# mpcie-breakout.net
KiCad netlist of a schematic drawn in EAGLE
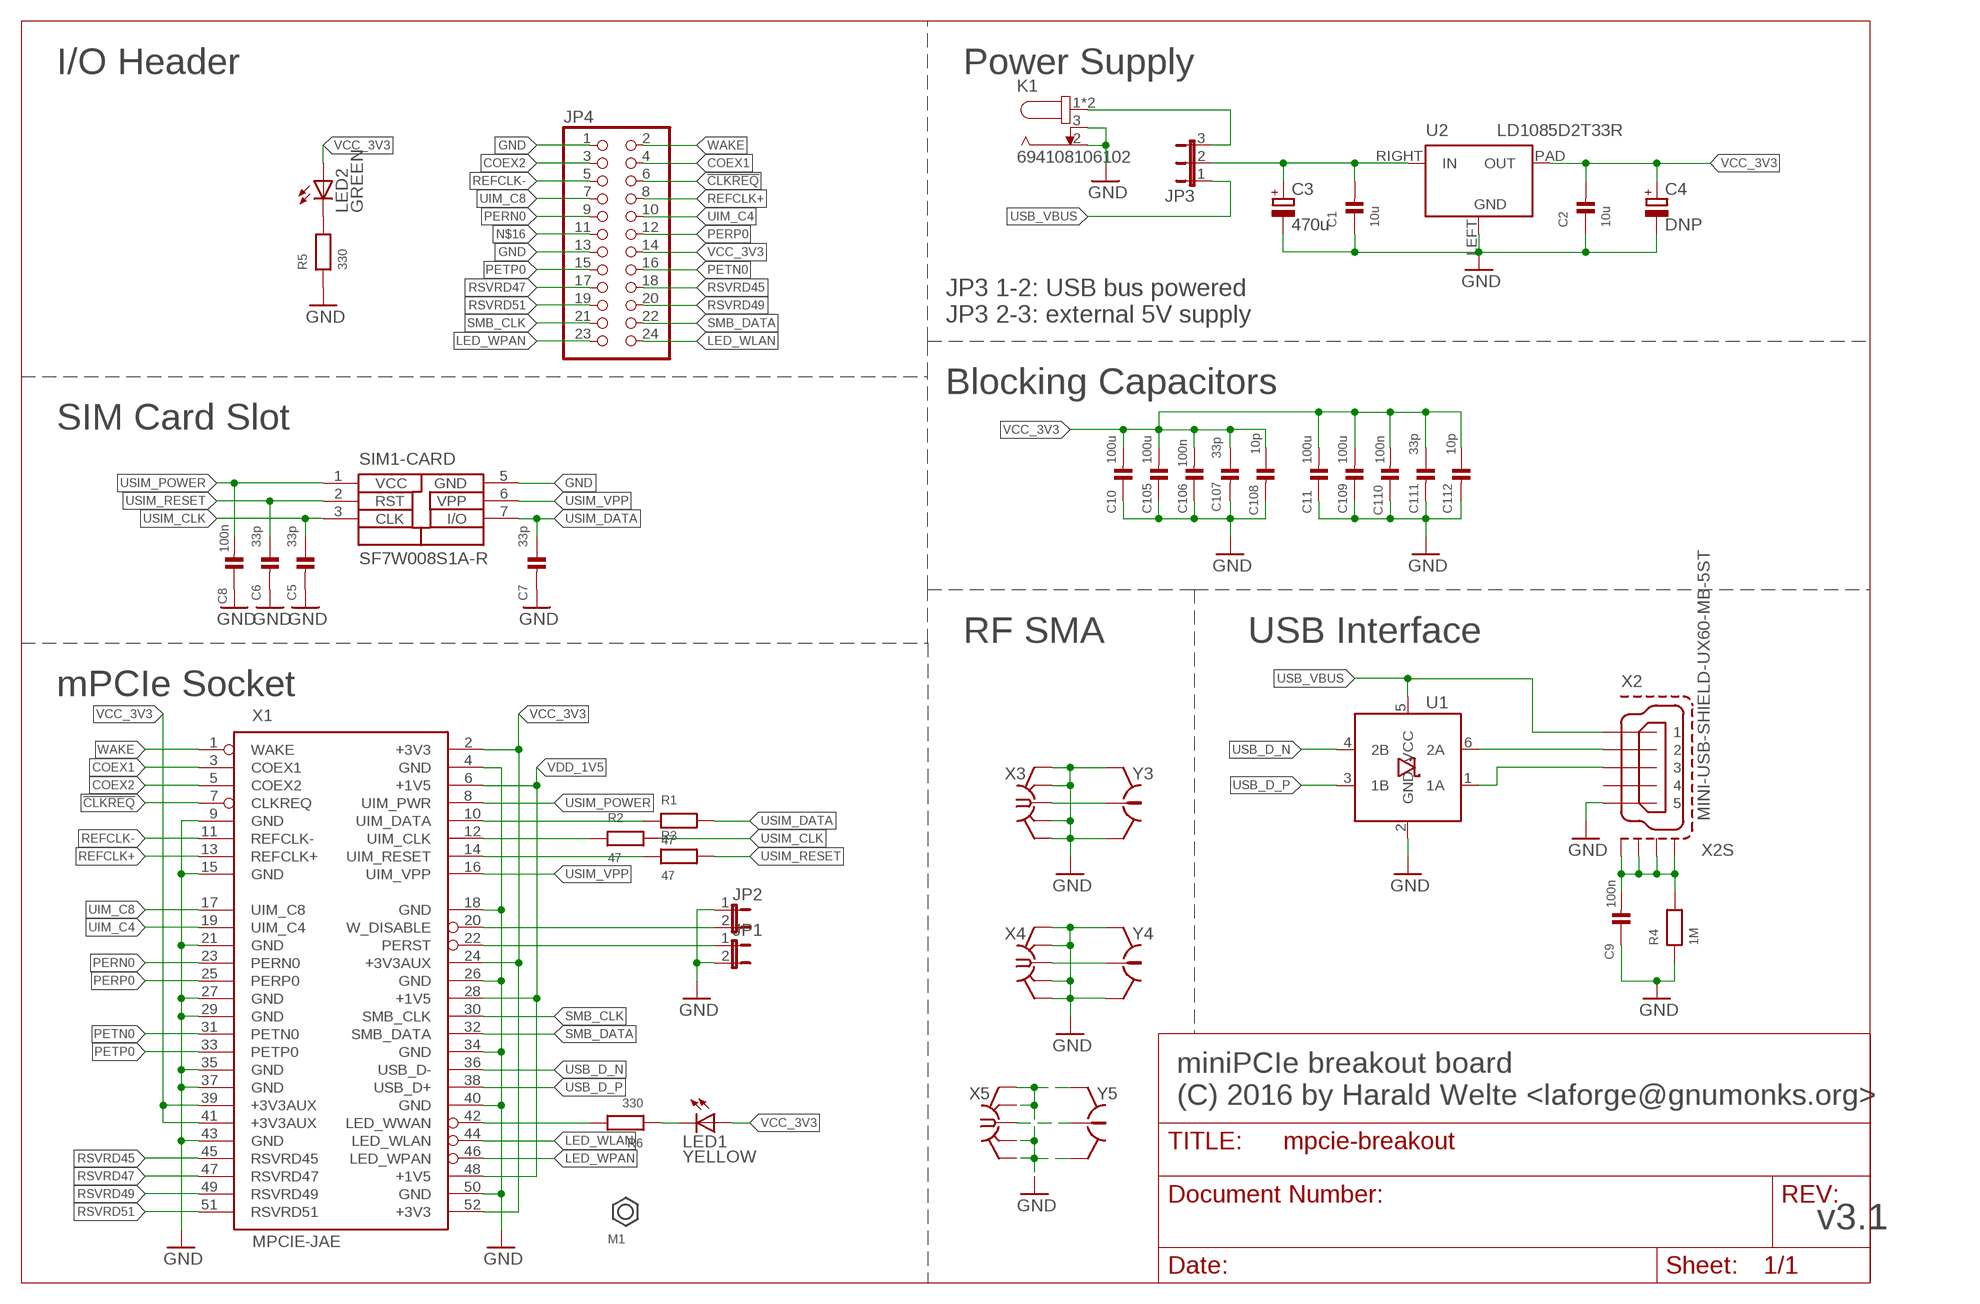
[diagram p0: schematic, sheet 1]

(export (version "E")
  (design (tool "Eeschema 10.0.6"))
  (components
    (comp (ref "C1")
      (value "10u")
      (footprint "eagle-import:_0805")
      (description "10µF 16V Ceramic Capacitor X5R 0805 (2012 Metric) 0.079\" L x 0.049\" W (2.00mm x 1.25mm)")
      (fields
        (field (name "MANUFACTURER") "Samsung Electro-Mechanics America, Inc.")
        (field (name "MANUFACTURERPARTNUMBER") "CL21A106KOQNNNG")
      )
      (libsource (lib "eagle-import") (part "CAP_CERAMIC_0805"))
    )
    (comp (ref "C2")
      (value "10u")
      (footprint "eagle-import:_0805")
      (description "10µF 16V Ceramic Capacitor X5R 0805 (2012 Metric) 0.079\" L x 0.049\" W (2.00mm x 1.25mm)")
      (fields
        (field (name "MANUFACTURER") "Samsung Electro-Mechanics America, Inc.")
        (field (name "MANUFACTURERPARTNUMBER") "CL21A106KOQNNNG")
      )
      (libsource (lib "eagle-import") (part "CAP_CERAMIC_0805"))
    )
    (comp (ref "C3")
      (value "470u")
      (footprint "eagle-import:UD-8X10_NICHICON")
      (description "470µF 6.3V Aluminum Capacitors Radial, Can - SMD  2000 Hrs @ 85°C")
      (fields
        (field (name "MANUFACTURER") "Nichicon")
        (field (name "MANUFACTURERPARTNUMBER") "UUR0J471MNL1GS")
      )
      (libsource (lib "eagle-import") (part "CPOL-EUUD-8X10"))
    )
    (comp (ref "C4")
      (value "DNP")
      (footprint "eagle-import:SMC_E")
      (description "NO DESCRIPTION")
      (fields
        (field (name "MANUFACTURER") "UNKNOWN MANUFACTURER")
        (field (name "MANUFACTURERPARTNUMBER") "UNKNOWN MANUFACTURER PART NUMBER")
      )
      (libsource (lib "eagle-import") (part "CPOL-EUSMCE"))
    )
    (comp (ref "C5")
      (value "33p")
      (footprint "eagle-import:_0402")
      (description "CAP CER 33PF 50V NP0 0402")
      (fields
        (field (name "MANUFACTURER") "Samsung Electro-Mechanics America, Inc.")
        (field (name "MANUFACTURERPARTNUMBER") "CL05C330JB5NNNC")
      )
      (libsource (lib "eagle-import") (part "CAP_CERAMIC_0402"))
    )
    (comp (ref "C6")
      (value "33p")
      (footprint "eagle-import:_0402")
      (description "CAP CER 33PF 50V NP0 0402")
      (fields
        (field (name "MANUFACTURER") "Samsung Electro-Mechanics America, Inc.")
        (field (name "MANUFACTURERPARTNUMBER") "CL05C330JB5NNNC")
      )
      (libsource (lib "eagle-import") (part "CAP_CERAMIC_0402"))
    )
    (comp (ref "C7")
      (value "33p")
      (footprint "eagle-import:_0402")
      (description "CAP CER 33PF 50V NP0 0402")
      (fields
        (field (name "MANUFACTURER") "Samsung Electro-Mechanics America, Inc.")
        (field (name "MANUFACTURERPARTNUMBER") "CL05C330JB5NNNC")
      )
      (libsource (lib "eagle-import") (part "CAP_CERAMIC_0402"))
    )
    (comp (ref "C8")
      (value "100n")
      (footprint "eagle-import:_0603")
      (description "CAP CER 0.1UF 16V 10% X7R 0603")
      (fields
        (field (name "MANUFACTURER") "Samsung Electro-Mechanics America, Inc")
        (field (name "MANUFACTURERPARTNUMBER") "CL10B104KO8NNNC")
      )
      (libsource (lib "eagle-import") (part "CAP_CERAMIC_0603"))
    )
    (comp (ref "C9")
      (value "100n")
      (footprint "eagle-import:_0603")
      (description "CAP CER 0.1UF 16V 10% X7R 0603")
      (fields
        (field (name "MANUFACTURER") "Samsung Electro-Mechanics America, Inc")
        (field (name "MANUFACTURERPARTNUMBER") "CL10B104KO8NNNC")
      )
      (libsource (lib "eagle-import") (part "CAP_CERAMIC_0603"))
    )
    (comp (ref "C10")
      (value "100u")
      (footprint "eagle-import:1206")
      (description "100µF 6.3V Ceramic Capacitor X5R 1206 (3216 Metric) 0.126\" L x 0.063\" W (3.20mm x 1.60mm)")
      (fields
        (field (name "MANUFACTURER") "Murata Electronics North America")
        (field (name "MANUFACTURERPARTNUMBER") "GRM31CR60J107ME39K")
      )
      (libsource (lib "eagle-import") (part "CAP_CERAMIC1206"))
    )
    (comp (ref "C11")
      (value "100u")
      (footprint "eagle-import:1206")
      (description "100µF 6.3V Ceramic Capacitor X5R 1206 (3216 Metric) 0.126\" L x 0.063\" W (3.20mm x 1.60mm)")
      (fields
        (field (name "MANUFACTURER") "Murata Electronics North America")
        (field (name "MANUFACTURERPARTNUMBER") "GRM31CR60J107ME39K")
      )
      (libsource (lib "eagle-import") (part "CAP_CERAMIC1206"))
    )
    (comp (ref "C105")
      (value "100u")
      (footprint "eagle-import:1206")
      (description "100µF 6.3V Ceramic Capacitor X5R 1206 (3216 Metric) 0.126\" L x 0.063\" W (3.20mm x 1.60mm)")
      (fields
        (field (name "MANUFACTURER") "Murata Electronics North America")
        (field (name "MANUFACTURERPARTNUMBER") "GRM31CR60J107ME39K")
      )
      (libsource (lib "eagle-import") (part "CAP_CERAMIC1206"))
    )
    (comp (ref "C106")
      (value "100n")
      (footprint "eagle-import:_0603")
      (description "CAP CER 0.1UF 16V 10% X7R 0603")
      (fields
        (field (name "MANUFACTURER") "Samsung Electro-Mechanics America, Inc")
        (field (name "MANUFACTURERPARTNUMBER") "CL10B104KO8NNNC")
      )
      (libsource (lib "eagle-import") (part "CAP_CERAMIC_0603"))
    )
    (comp (ref "C107")
      (value "33p")
      (footprint "eagle-import:_0402")
      (description "CAP CER 33PF 50V NP0 0402")
      (fields
        (field (name "MANUFACTURER") "Samsung Electro-Mechanics America, Inc.")
        (field (name "MANUFACTURERPARTNUMBER") "CL05C330JB5NNNC")
      )
      (libsource (lib "eagle-import") (part "CAP_CERAMIC_0402"))
    )
    (comp (ref "C108")
      (value "10p")
      (footprint "eagle-import:_0603")
      (description "CAP CER 10PF 50V NP0 0603")
      (fields
        (field (name "MANUFACTURER") "Kemet")
        (field (name "MANUFACTURERPARTNUMBER") "C0603C100J5GACTU")
      )
      (libsource (lib "eagle-import") (part "CAP_CERAMIC_0603"))
    )
    (comp (ref "C109")
      (value "100u")
      (footprint "eagle-import:1206")
      (description "100µF 6.3V Ceramic Capacitor X5R 1206 (3216 Metric) 0.126\" L x 0.063\" W (3.20mm x 1.60mm)")
      (fields
        (field (name "MANUFACTURER") "Murata Electronics North America")
        (field (name "MANUFACTURERPARTNUMBER") "GRM31CR60J107ME39K")
      )
      (libsource (lib "eagle-import") (part "CAP_CERAMIC1206"))
    )
    (comp (ref "C110")
      (value "100n")
      (footprint "eagle-import:_0603")
      (description "CAP CER 0.1UF 16V 10% X7R 0603")
      (fields
        (field (name "MANUFACTURER") "Samsung Electro-Mechanics America, Inc")
        (field (name "MANUFACTURERPARTNUMBER") "CL10B104KO8NNNC")
      )
      (libsource (lib "eagle-import") (part "CAP_CERAMIC_0603"))
    )
    (comp (ref "C111")
      (value "33p")
      (footprint "eagle-import:_0402")
      (description "CAP CER 33PF 50V NP0 0402")
      (fields
        (field (name "MANUFACTURER") "Samsung Electro-Mechanics America, Inc.")
        (field (name "MANUFACTURERPARTNUMBER") "CL05C330JB5NNNC")
      )
      (libsource (lib "eagle-import") (part "CAP_CERAMIC_0402"))
    )
    (comp (ref "C112")
      (value "10p")
      (footprint "eagle-import:_0603")
      (description "CAP CER 10PF 50V NP0 0603")
      (fields
        (field (name "MANUFACTURER") "Kemet")
        (field (name "MANUFACTURERPARTNUMBER") "C0603C100J5GACTU")
      )
      (libsource (lib "eagle-import") (part "CAP_CERAMIC_0603"))
    )
    (comp (ref "JP1")
      (value "JP1E")
      (footprint "eagle-import:JP1")
      (description "NO DESCRIPTION")
      (fields
        (field (name "MANUFACTURER") "UNKNOWN MANUFACTURER")
        (field (name "MANUFACTURERPARTNUMBER") "UNKNOWN MANUFACTURER PART NUMBER")
      )
      (libsource (lib "eagle-import") (part "JP1E"))
    )
    (comp (ref "JP2")
      (value "JP1E")
      (footprint "eagle-import:JP1")
      (description "NO DESCRIPTION")
      (fields
        (field (name "MANUFACTURER") "UNKNOWN MANUFACTURER")
        (field (name "MANUFACTURERPARTNUMBER") "UNKNOWN MANUFACTURER PART NUMBER")
      )
      (libsource (lib "eagle-import") (part "JP1E"))
    )
    (comp (ref "JP3")
      (value "JP2E")
      (footprint "eagle-import:JP2")
      (description "NO DESCRIPTION")
      (fields
        (field (name "MANUFACTURER") "UNKNOWN MANUFACTURER")
        (field (name "MANUFACTURERPARTNUMBER") "UNKNOWN MANUFACTURER PART NUMBER")
      )
      (libsource (lib "eagle-import") (part "JP2E"))
    )
    (comp (ref "JP4")
      (value "PINHD-2X12")
      (footprint "eagle-import:2X12")
      (description "24 Positions Header, Unshrouded Connector 0.100\" (2.54mm) Through Hole Gold")
      (fields (field (name "MANUFACTURER") "3M") (field (name "MANUFACTURERPARTNUMBER") "961224-6404-AR"))
      (libsource (lib "eagle-import") (part "PINHD-2X12"))
    )
    (comp (ref "K1")
      (value "694108106102")
      (footprint "eagle-import:694108106102")
      (description "Power Barrel Connector Jack 2.50mm ID (0.098\"), 5.50mm OD (0.217\") Surface Mount, Right Angle")
      (fields (field (name "MANUFACTURER") "Wurth Electronics Inc"))
      (libsource (lib "eagle-import") (part "694108106102"))
    )
    (comp (ref "LED1")
      (value "YELLOW")
      (footprint "eagle-import:CHIP-LED0603")
      (description "NO DESCRIPTION")
      (fields
        (field (name "MANUFACTURER") "UNKNOWN MANUFACTURER")
        (field (name "MANUFACTURERPARTNUMBER") "UNKNOWN MANUFACTURER PART NUMBER")
      )
      (libsource (lib "eagle-import") (part "LEDCHIP-LED0603"))
    )
    (comp (ref "LED2")
      (value "GREEN")
      (footprint "eagle-import:CHIP-LED0603")
      (description "NO DESCRIPTION")
      (fields
        (field (name "MANUFACTURER") "UNKNOWN MANUFACTURER")
        (field (name "MANUFACTURERPARTNUMBER") "UNKNOWN MANUFACTURER PART NUMBER")
      )
      (libsource (lib "eagle-import") (part "LEDCHIP-LED0603"))
    )
    (comp (ref "R1")
      (value "47")
      (footprint "eagle-import:_0603")
      (description "RES SMD 47 OHM 5% 1/10W 0603")
      (fields (field (name "MANUFACTURER") "Yageo") (field (name "MANUFACTURERPARTNUMBER") "RC0603JR-0747RL"))
      (libsource (lib "eagle-import") (part "RESISTOR_0603"))
    )
    (comp (ref "R2")
      (value "47")
      (footprint "eagle-import:_0603")
      (description "RES SMD 47 OHM 5% 1/10W 0603")
      (fields (field (name "MANUFACTURER") "Yageo") (field (name "MANUFACTURERPARTNUMBER") "RC0603JR-0747RL"))
      (libsource (lib "eagle-import") (part "RESISTOR_0603"))
    )
    (comp (ref "R3")
      (value "47")
      (footprint "eagle-import:_0603")
      (description "RES SMD 47 OHM 5% 1/10W 0603")
      (fields (field (name "MANUFACTURER") "Yageo") (field (name "MANUFACTURERPARTNUMBER") "RC0603JR-0747RL"))
      (libsource (lib "eagle-import") (part "RESISTOR_0603"))
    )
    (comp (ref "R4")
      (value "1M")
      (footprint "eagle-import:_0603")
      (description "RES SMD 1M OHM 5% 1/10W 0603")
      (fields (field (name "MANUFACTURER") "Yageo") (field (name "MANUFACTURERPARTNUMBER") "RC0603JR-071ML"))
      (libsource (lib "eagle-import") (part "RESISTOR_0603"))
    )
    (comp (ref "R5")
      (value "330")
      (footprint "eagle-import:_0603")
      (description "RES SMD 330 OHM 5% 1/10W 0603")
      (fields
        (field (name "MANUFACTURER") "Yageo")
        (field (name "MANUFACTURERPARTNUMBER") "RC0603JR-07330RL")
      )
      (libsource (lib "eagle-import") (part "RESISTOR_0603"))
    )
    (comp (ref "R6")
      (value "330")
      (footprint "eagle-import:_0603")
      (description "RES SMD 330 OHM 5% 1/10W 0603")
      (fields
        (field (name "MANUFACTURER") "Yageo")
        (field (name "MANUFACTURERPARTNUMBER") "RC0603JR-07330RL")
      )
      (libsource (lib "eagle-import") (part "RESISTOR_0603"))
    )
    (comp (ref "SIM1")
      (value "SF7W008S1A-R")
      (footprint "eagle-import:SF7W008S1A-RESTR")
      (description "8 (6 + 2) Position Card Connector SIM Card Surface Mount, Right Angle Gold")
      (fields
        (field (name "MANUFACTURER") "JAE Electronics")
        (field (name "MANUFACTURERPARTNUMBER") "SF7W008S1AE900")
      )
      (libsource (lib "eagle-import") (part "SF7W008S1A-R"))
    )
    (comp (ref "U1")
      (value "IP4234CZ6")
      (footprint "eagle-import:TSOP-6")
      (description "TVS DIODE 5.5VWM 6TSOP")
      (fields
        (field (name "MANUFACTURER") "NXP Semiconductors")
        (field (name "MANUFACTURERPARTNUMBER") "IP4234CZ6,125")
      )
      (libsource (lib "eagle-import") (part "IP4234CZ6"))
    )
    (comp (ref "U2")
      (value "LD1085D2T33R")
      (footprint "eagle-import:ST_D2PAK")
      (description "Linear Voltage Regulator IC Positive Fixed 1 Output 3.3V 3A D2PAK")
      (fields (field (name "MANUFACTURER") "STMicroelectronics"))
      (libsource (lib "eagle-import") (part "LDO-LD1085D2"))
    )
    (comp (ref "X1")
      (value "MPCIE-JAE")
      (footprint "eagle-import:MM60-52")
      (description "CONN MINI EXPRESS CARD 52POS SMD")
      (fields
        (field (name "MANUFACTURER") "JAE Electronics")
        (field (name "MANUFACTURERPARTNUMBER") "MM60-52B1-E1-R650")
      )
      (libsource (lib "eagle-import") (part "MPCIE-JAE"))
    )
    (comp (ref "X2")
      (value "MINI-USB-SHIELD-UX60-MB-5ST")
      (footprint "eagle-import:UX60-MB-5ST")
      (description "USB - mini B USB 2.0 Receptacle Connector 5 Position Surface Mount, Right Angle, Horizontal")
      (fields
        (field (name "CLASS") "CONNECTOR")
        (field (name "LINK") "http://www.digikey.com/product-detail/en/hirose-electric-co-ltd/UX60-MB-5ST/H2959CT-ND/597538")
        (field (name "MANUFACTURER") "Hirose Electric Co Ltd")
        (field (name "MANUFACTURERPARTNUMBER") "UX60-MB-5ST")
        (field (name "POPULATED") "TRUE")
        (field (name "ROHSCERTIFICATE") "UNKNOWN ROHS CERTIFICATE")
        (field (name "SOURCE") "DIGIKEY")
        (field (name "SOURCEPARTNUMBER") "H2959CT-ND")
      )
      (libsource (lib "eagle-import") (part "MINI-USB-SHIELD-UX60-MB-5ST"))
    )
    (comp (ref "X3")
      (value "SMA-F-S-TH")
      (footprint "eagle-import:SMA-F-S-TH")
      (description "CONN SMA JACK STR 50 OHM PCB")
      (fields
        (field (name "MANUFACTURER") "TE Connectivity AMP Connectors")
        (field (name "MANUFACTURERPARTNUMBER") "5-1814832-1")
      )
      (libsource (lib "eagle-import") (part "SMA-F-S-TH"))
    )
    (comp (ref "X4")
      (value "SMA-F-S-TH")
      (footprint "eagle-import:SMA-F-S-TH")
      (description "CONN SMA JACK STR 50 OHM PCB")
      (fields
        (field (name "MANUFACTURER") "TE Connectivity AMP Connectors")
        (field (name "MANUFACTURERPARTNUMBER") "5-1814832-1")
      )
      (libsource (lib "eagle-import") (part "SMA-F-S-TH"))
    )
    (comp (ref "X5")
      (value "SMA-F-S-TH")
      (footprint "eagle-import:SMA-F-S-TH")
      (description "CONN SMA JACK STR 50 OHM PCB")
      (fields
        (field (name "MANUFACTURER") "TE Connectivity AMP Connectors")
        (field (name "MANUFACTURERPARTNUMBER") "5-1814832-1")
      )
      (libsource (lib "eagle-import") (part "SMA-F-S-TH"))
    )
    (comp (ref "Y3")
      (value "HRS_UFL")
      (footprint "eagle-import:HRS_UFL")
      (description "CONN UMC RCPT STR 50 OHM SMD")
      (fields
        (field (name "MANUFACTURER") "Hirose Electric Co Ltd")
        (field (name "MANUFACTURERPARTNUMBER") "U.FL-R-SMT(01)")
      )
      (libsource (lib "eagle-import") (part "HRS_UFL"))
    )
    (comp (ref "Y4")
      (value "HRS_UFL")
      (footprint "eagle-import:HRS_UFL")
      (description "CONN UMC RCPT STR 50 OHM SMD")
      (fields
        (field (name "MANUFACTURER") "Hirose Electric Co Ltd")
        (field (name "MANUFACTURERPARTNUMBER") "U.FL-R-SMT(01)")
      )
      (libsource (lib "eagle-import") (part "HRS_UFL"))
    )
    (comp (ref "Y5")
      (value "HRS_UFL")
      (footprint "eagle-import:HRS_UFL")
      (description "CONN UMC RCPT STR 50 OHM SMD")
      (fields
        (field (name "MANUFACTURER") "Hirose Electric Co Ltd")
        (field (name "MANUFACTURERPARTNUMBER") "U.FL-R-SMT(01)")
      )
      (libsource (lib "eagle-import") (part "HRS_UFL"))
    )
  )
  (nets
    (net (code "1") (name "/~{CLKREQ}") (class "Default")
      (node (ref "JP4") (pin "6") (pinfunction "6_6") (pintype "passive"))
      (node (ref "X1") (pin "7") (pinfunction "CLKREQ_7") (pintype "output"))
    )
    (net (code "2") (name "COEX1") (class "Default")
      (node (ref "JP4") (pin "4") (pinfunction "4_4") (pintype "passive"))
      (node (ref "X1") (pin "3") (pinfunction "COEX1_3") (pintype "bidirectional"))
    )
    (net (code "3") (name "COEX2") (class "Default")
      (node (ref "JP4") (pin "3") (pinfunction "3_3") (pintype "passive"))
      (node (ref "X1") (pin "5") (pinfunction "COEX2_5") (pintype "bidirectional"))
    )
    (net (code "4") (name "GND") (class "Default")
      (node (ref "C1") (pin "1") (pinfunction "1_1") (pintype "passive"))
      (node (ref "C10") (pin "1") (pinfunction "1_1") (pintype "passive"))
      (node (ref "C105") (pin "1") (pinfunction "1_1") (pintype "passive"))
      (node (ref "C106") (pin "1") (pinfunction "1_1") (pintype "passive"))
      (node (ref "C107") (pin "2") (pinfunction "2_2") (pintype "passive"))
      (node (ref "C108") (pin "2") (pinfunction "2_2") (pintype "passive"))
      (node (ref "C109") (pin "1") (pinfunction "1_1") (pintype "passive"))
      (node (ref "C11") (pin "1") (pinfunction "1_1") (pintype "passive"))
      (node (ref "C110") (pin "1") (pinfunction "1_1") (pintype "passive"))
      (node (ref "C111") (pin "2") (pinfunction "2_2") (pintype "passive"))
      (node (ref "C112") (pin "2") (pinfunction "2_2") (pintype "passive"))
      (node (ref "C2") (pin "1") (pinfunction "1_1") (pintype "passive"))
      (node (ref "C3") (pin "-") (pinfunction "-_-") (pintype "passive"))
      (node (ref "C4") (pin "-") (pinfunction "-_-") (pintype "passive"))
      (node (ref "C5") (pin "2") (pinfunction "2_2") (pintype "passive"))
      (node (ref "C6") (pin "2") (pinfunction "2_2") (pintype "passive"))
      (node (ref "C7") (pin "2") (pinfunction "2_2") (pintype "passive"))
      (node (ref "C8") (pin "1") (pinfunction "1_1") (pintype "passive"))
      (node (ref "C9") (pin "1") (pinfunction "1_1") (pintype "passive"))
      (node (ref "JP1") (pin "2") (pinfunction "2_2") (pintype "passive"))
      (node (ref "JP2") (pin "1") (pinfunction "1_1") (pintype "passive"))
      (node (ref "JP4") (pin "1") (pinfunction "1_1") (pintype "passive"))
      (node (ref "JP4") (pin "13") (pinfunction "13_13") (pintype "passive"))
      (node (ref "K1") (pin "2") (pinfunction "2_2") (pintype "passive"))
      (node (ref "K1") (pin "3") (pinfunction "3_3") (pintype "passive"))
      (node (ref "R4") (pin "1") (pinfunction "1_1") (pintype "passive"))
      (node (ref "R5") (pin "1") (pinfunction "1_1") (pintype "passive"))
      (node (ref "SIM1") (pin "5") (pinfunction "GND_5") (pintype "power_in"))
      (node (ref "U1") (pin "2") (pinfunction "GND_2") (pintype "passive"))
      (node (ref "U2") (pin "LEFT") (pinfunction "GND_LEFT") (pintype "power_in"))
      (node (ref "X1") (pin "15") (pinfunction "GND_15") (pintype "power_in"))
      (node (ref "X1") (pin "18") (pinfunction "GND_18") (pintype "power_in"))
      (node (ref "X1") (pin "21") (pinfunction "GND_21") (pintype "power_in"))
      (node (ref "X1") (pin "26") (pinfunction "GND_26") (pintype "power_in"))
      (node (ref "X1") (pin "27") (pinfunction "GND_27") (pintype "power_in"))
      (node (ref "X1") (pin "29") (pinfunction "GND_29") (pintype "power_in"))
      (node (ref "X1") (pin "34") (pinfunction "GND_34") (pintype "bidirectional"))
      (node (ref "X1") (pin "35") (pinfunction "GND_35") (pintype "power_in"))
      (node (ref "X1") (pin "37") (pinfunction "GND_37") (pintype "power_in"))
      (node (ref "X1") (pin "4") (pinfunction "GND_4") (pintype "power_in"))
      (node (ref "X1") (pin "40") (pinfunction "GND_40") (pintype "power_in"))
      (node (ref "X1") (pin "43") (pinfunction "GND_43") (pintype "bidirectional"))
      (node (ref "X1") (pin "50") (pinfunction "GND_50") (pintype "power_in"))
      (node (ref "X1") (pin "9") (pinfunction "GND_9") (pintype "power_in"))
      (node (ref "X2") (pin "5") (pinfunction "5_5") (pintype "input"))
      (node (ref "X3") (pin "G1") (pinfunction "GND_G1") (pintype "power_in"))
      (node (ref "X3") (pin "G2") (pinfunction "GND_G2") (pintype "power_in"))
      (node (ref "X3") (pin "G3") (pinfunction "GND_G3") (pintype "power_in"))
      (node (ref "X3") (pin "G4") (pinfunction "GND_G4") (pintype "power_in"))
      (node (ref "X4") (pin "G1") (pinfunction "GND_G1") (pintype "power_in"))
      (node (ref "X4") (pin "G2") (pinfunction "GND_G2") (pintype "power_in"))
      (node (ref "X4") (pin "G3") (pinfunction "GND_G3") (pintype "power_in"))
      (node (ref "X4") (pin "G4") (pinfunction "GND_G4") (pintype "power_in"))
      (node (ref "X5") (pin "G1") (pinfunction "GND_G1") (pintype "power_in"))
      (node (ref "X5") (pin "G2") (pinfunction "GND_G2") (pintype "power_in"))
      (node (ref "X5") (pin "G3") (pinfunction "GND_G3") (pintype "power_in"))
      (node (ref "X5") (pin "G4") (pinfunction "GND_G4") (pintype "power_in"))
      (node (ref "Y3") (pin "GND@1") (pinfunction "GND_GND@1") (pintype "power_in"))
      (node (ref "Y3") (pin "GND@2") (pinfunction "GND_GND@2") (pintype "power_in"))
      (node (ref "Y4") (pin "GND@1") (pinfunction "GND_GND@1") (pintype "power_in"))
      (node (ref "Y4") (pin "GND@2") (pinfunction "GND_GND@2") (pintype "power_in"))
      (node (ref "Y5") (pin "GND@1") (pinfunction "GND_GND@1") (pintype "power_in"))
      (node (ref "Y5") (pin "GND@2") (pinfunction "GND_GND@2") (pintype "power_in"))
    )
    (net (code "5") (name "LED_WLAN") (class "Default")
      (node (ref "JP4") (pin "24") (pinfunction "24_24") (pintype "passive"))
      (node (ref "X1") (pin "44") (pinfunction "LED_WLAN_44") (pintype "output"))
    )
    (net (code "6") (name "LED_WPAN") (class "Default")
      (node (ref "JP4") (pin "23") (pinfunction "23_23") (pintype "passive"))
      (node (ref "X1") (pin "46") (pinfunction "LED_WPAN_46") (pintype "output"))
    )
    (net (code "7") (name "N$16") (class "Default")
      (node (ref "JP4") (pin "11") (pinfunction "11_11") (pintype "passive"))
    )
    (net (code "8") (name "Net-(JP3-Pad3)") (class "Default")
      (node (ref "JP3") (pin "3") (pinfunction "3_3") (pintype "passive"))
      (node (ref "K1") (pin "1") (pinfunction "1_1") (pintype "passive"))
      (node (ref "K1") (pin "1-1") (pinfunction "1_1-1") (pintype "passive"))
    )
    (net (code "9") (name "Net-(LED1-PadC)") (class "Default")
      (node (ref "LED1") (pin "C") (pinfunction "C_C") (pintype "passive"))
      (node (ref "R6") (pin "1") (pinfunction "1_1") (pintype "passive"))
    )
    (net (code "10") (name "Net-(LED2-PadC)") (class "Default")
      (node (ref "LED2") (pin "C") (pinfunction "C_C") (pintype "passive"))
      (node (ref "R5") (pin "2") (pinfunction "2_2") (pintype "passive"))
    )
    (net (code "11") (name "Net-(U1-1A)") (class "Default")
      (node (ref "U1") (pin "1") (pinfunction "1A_1") (pintype "passive"))
      (node (ref "X2") (pin "3") (pinfunction "3_3") (pintype "input"))
    )
    (net (code "12") (name "Net-(U1-2A)") (class "Default")
      (node (ref "U1") (pin "6") (pinfunction "2A_6") (pintype "passive"))
      (node (ref "X2") (pin "2") (pinfunction "2_2") (pintype "input"))
    )
    (net (code "13") (name "Net-(U2-IN)") (class "Default")
      (node (ref "C1") (pin "2") (pinfunction "2_2") (pintype "passive"))
      (node (ref "C3") (pin "+") (pinfunction "+_+") (pintype "passive"))
      (node (ref "JP3") (pin "2") (pinfunction "2_2") (pintype "passive"))
      (node (ref "U2") (pin "RIGHT") (pinfunction "IN_RIGHT") (pintype "input"))
    )
    (net (code "14") (name "Net-(X1-LED_WWAN)") (class "Default")
      (node (ref "R6") (pin "2") (pinfunction "2_2") (pintype "passive"))
      (node (ref "X1") (pin "42") (pinfunction "LED_WWAN_42") (pintype "output"))
    )
    (net (code "15") (name "Net-(X1-PERST)") (class "Default")
      (node (ref "JP1") (pin "1") (pinfunction "1_1") (pintype "passive"))
      (node (ref "X1") (pin "22") (pinfunction "PERST_22") (pintype "input"))
    )
    (net (code "16") (name "Net-(X1-UIM_CLK)") (class "Default")
      (node (ref "R2") (pin "1") (pinfunction "1_1") (pintype "passive"))
      (node (ref "X1") (pin "12") (pinfunction "UIM_CLK_12") (pintype "bidirectional"))
    )
    (net (code "17") (name "Net-(X1-UIM_DATA)") (class "Default")
      (node (ref "R1") (pin "1") (pinfunction "1_1") (pintype "passive"))
      (node (ref "X1") (pin "10") (pinfunction "UIM_DATA_10") (pintype "bidirectional"))
    )
    (net (code "18") (name "Net-(X1-UIM_RESET)") (class "Default")
      (node (ref "R3") (pin "1") (pinfunction "1_1") (pintype "passive"))
      (node (ref "X1") (pin "14") (pinfunction "UIM_RESET_14") (pintype "bidirectional"))
    )
    (net (code "19") (name "Net-(X1-W_DISABLE)") (class "Default")
      (node (ref "JP2") (pin "2") (pinfunction "2_2") (pintype "passive"))
      (node (ref "X1") (pin "20") (pinfunction "W_DISABLE_20") (pintype "input"))
    )
    (net (code "20") (name "Net-(X2B-S1)") (class "Default")
      (node (ref "C9") (pin "2") (pinfunction "2_2") (pintype "passive"))
      (node (ref "R4") (pin "2") (pinfunction "2_2") (pintype "passive"))
      (node (ref "X2") (pin "M1") (pinfunction "S1_M1") (pintype "passive"))
      (node (ref "X2") (pin "M2") (pinfunction "S2_M2") (pintype "passive"))
      (node (ref "X2") (pin "M3") (pinfunction "S3_M3") (pintype "passive"))
      (node (ref "X2") (pin "M4") (pinfunction "S4_M4") (pintype "passive"))
    )
    (net (code "21") (name "Net-(X3-1)") (class "Default")
      (node (ref "X3") (pin "C") (pinfunction "1_C") (pintype "passive"))
      (node (ref "Y3") (pin "SIG") (pinfunction "1_SIG") (pintype "passive"))
    )
    (net (code "22") (name "Net-(X4-1)") (class "Default")
      (node (ref "X4") (pin "C") (pinfunction "1_C") (pintype "passive"))
      (node (ref "Y4") (pin "SIG") (pinfunction "1_SIG") (pintype "passive"))
    )
    (net (code "23") (name "Net-(X5-1)") (class "Default")
      (node (ref "X5") (pin "C") (pinfunction "1_C") (pintype "passive"))
      (node (ref "Y5") (pin "SIG") (pinfunction "1_SIG") (pintype "passive"))
    )
    (net (code "24") (name "PERN0") (class "Default")
      (node (ref "JP4") (pin "9") (pinfunction "9_9") (pintype "passive"))
      (node (ref "X1") (pin "23") (pinfunction "PERN0_23") (pintype "bidirectional"))
    )
    (net (code "25") (name "PERP0") (class "Default")
      (node (ref "JP4") (pin "12") (pinfunction "12_12") (pintype "passive"))
      (node (ref "X1") (pin "25") (pinfunction "PERP0_25") (pintype "bidirectional"))
    )
    (net (code "26") (name "PETN0") (class "Default")
      (node (ref "JP4") (pin "16") (pinfunction "16_16") (pintype "passive"))
      (node (ref "X1") (pin "31") (pinfunction "PETN0_31") (pintype "bidirectional"))
    )
    (net (code "27") (name "PETP0") (class "Default")
      (node (ref "JP4") (pin "15") (pinfunction "15_15") (pintype "passive"))
      (node (ref "X1") (pin "33") (pinfunction "PETP0_33") (pintype "bidirectional"))
    )
    (net (code "28") (name "REFCLK+") (class "Default")
      (node (ref "JP4") (pin "8") (pinfunction "8_8") (pintype "passive"))
      (node (ref "X1") (pin "13") (pinfunction "REFCLK+_13") (pintype "input"))
    )
    (net (code "29") (name "REFCLK-") (class "Default")
      (node (ref "JP4") (pin "5") (pinfunction "5_5") (pintype "passive"))
      (node (ref "X1") (pin "11") (pinfunction "REFCLK-_11") (pintype "input"))
    )
    (net (code "30") (name "RSVRD45") (class "Default")
      (node (ref "JP4") (pin "18") (pinfunction "18_18") (pintype "passive"))
      (node (ref "X1") (pin "45") (pinfunction "RSVRD45_45") (pintype "bidirectional"))
    )
    (net (code "31") (name "RSVRD47") (class "Default")
      (node (ref "JP4") (pin "17") (pinfunction "17_17") (pintype "passive"))
      (node (ref "X1") (pin "47") (pinfunction "RSVRD47_47") (pintype "bidirectional"))
    )
    (net (code "32") (name "RSVRD49") (class "Default")
      (node (ref "JP4") (pin "20") (pinfunction "20_20") (pintype "passive"))
      (node (ref "X1") (pin "49") (pinfunction "RSVRD49_49") (pintype "bidirectional"))
    )
    (net (code "33") (name "RSVRD51") (class "Default")
      (node (ref "JP4") (pin "19") (pinfunction "19_19") (pintype "passive"))
      (node (ref "X1") (pin "51") (pinfunction "RSVRD51_51") (pintype "bidirectional"))
    )
    (net (code "34") (name "SMB_CLK") (class "Default")
      (node (ref "JP4") (pin "21") (pinfunction "21_21") (pintype "passive"))
      (node (ref "X1") (pin "30") (pinfunction "SMB_CLK_30") (pintype "input"))
    )
    (net (code "35") (name "SMB_DATA") (class "Default")
      (node (ref "JP4") (pin "22") (pinfunction "22_22") (pintype "passive"))
      (node (ref "X1") (pin "32") (pinfunction "SMB_DATA_32") (pintype "bidirectional"))
    )
    (net (code "36") (name "UIM_C4") (class "Default")
      (node (ref "JP4") (pin "10") (pinfunction "10_10") (pintype "passive"))
      (node (ref "X1") (pin "19") (pinfunction "UIM_C4_19") (pintype "bidirectional"))
    )
    (net (code "37") (name "UIM_C8") (class "Default")
      (node (ref "JP4") (pin "7") (pinfunction "7_7") (pintype "passive"))
      (node (ref "X1") (pin "17") (pinfunction "UIM_C8_17") (pintype "bidirectional"))
    )
    (net (code "38") (name "USB_D_N") (class "Default")
      (node (ref "U1") (pin "4") (pinfunction "2B_4") (pintype "passive"))
      (node (ref "X1") (pin "36") (pinfunction "USB_D-_36") (pintype "bidirectional"))
    )
    (net (code "39") (name "USB_D_P") (class "Default")
      (node (ref "U1") (pin "3") (pinfunction "1B_3") (pintype "passive"))
      (node (ref "X1") (pin "38") (pinfunction "USB_D+_38") (pintype "bidirectional"))
    )
    (net (code "40") (name "USB_VBUS") (class "Default")
      (node (ref "JP3") (pin "1") (pinfunction "1_1") (pintype "passive"))
      (node (ref "U1") (pin "5") (pinfunction "VCC_5") (pintype "passive"))
      (node (ref "X2") (pin "1") (pinfunction "1_1") (pintype "input"))
    )
    (net (code "41") (name "USIM_CLK") (class "Default")
      (node (ref "C5") (pin "1") (pinfunction "1_1") (pintype "passive"))
      (node (ref "R2") (pin "2") (pinfunction "2_2") (pintype "passive"))
      (node (ref "SIM1") (pin "3") (pinfunction "CLK_3") (pintype "input"))
    )
    (net (code "42") (name "USIM_DATA") (class "Default")
      (node (ref "C7") (pin "1") (pinfunction "1_1") (pintype "passive"))
      (node (ref "R1") (pin "2") (pinfunction "2_2") (pintype "passive"))
      (node (ref "SIM1") (pin "7") (pinfunction "I/O_7") (pintype "bidirectional"))
    )
    (net (code "43") (name "USIM_POWER") (class "Default")
      (node (ref "C8") (pin "2") (pinfunction "2_2") (pintype "passive"))
      (node (ref "SIM1") (pin "1") (pinfunction "VCC_1") (pintype "power_in"))
      (node (ref "X1") (pin "8") (pinfunction "UIM_PWR_8") (pintype "bidirectional"))
    )
    (net (code "44") (name "USIM_RESET") (class "Default")
      (node (ref "C6") (pin "1") (pinfunction "1_1") (pintype "passive"))
      (node (ref "R3") (pin "2") (pinfunction "2_2") (pintype "passive"))
      (node (ref "SIM1") (pin "2") (pinfunction "RST_2") (pintype "input"))
    )
    (net (code "45") (name "USIM_VPP") (class "Default")
      (node (ref "SIM1") (pin "6") (pinfunction "VPP_6") (pintype "power_in"))
      (node (ref "X1") (pin "16") (pinfunction "UIM_VPP_16") (pintype "bidirectional"))
    )
    (net (code "46") (name "VCC_3V3") (class "Default")
      (node (ref "C10") (pin "2") (pinfunction "2_2") (pintype "passive"))
      (node (ref "C105") (pin "2") (pinfunction "2_2") (pintype "passive"))
      (node (ref "C106") (pin "2") (pinfunction "2_2") (pintype "passive"))
      (node (ref "C107") (pin "1") (pinfunction "1_1") (pintype "passive"))
      (node (ref "C108") (pin "1") (pinfunction "1_1") (pintype "passive"))
      (node (ref "C109") (pin "2") (pinfunction "2_2") (pintype "passive"))
      (node (ref "C11") (pin "2") (pinfunction "2_2") (pintype "passive"))
      (node (ref "C110") (pin "2") (pinfunction "2_2") (pintype "passive"))
      (node (ref "C111") (pin "1") (pinfunction "1_1") (pintype "passive"))
      (node (ref "C112") (pin "1") (pinfunction "1_1") (pintype "passive"))
      (node (ref "C2") (pin "2") (pinfunction "2_2") (pintype "passive"))
      (node (ref "C4") (pin "+") (pinfunction "+_+") (pintype "passive"))
      (node (ref "JP4") (pin "14") (pinfunction "14_14") (pintype "passive"))
      (node (ref "LED1") (pin "A") (pinfunction "A_A") (pintype "passive"))
      (node (ref "LED2") (pin "A") (pinfunction "A_A") (pintype "passive"))
      (node (ref "U2") (pin "PAD") (pinfunction "OUT_PAD") (pintype "passive"))
      (node (ref "X1") (pin "2") (pinfunction "+3V3_2") (pintype "power_in"))
      (node (ref "X1") (pin "24") (pinfunction "+3V3AUX_24") (pintype "power_in"))
      (node (ref "X1") (pin "39") (pinfunction "+3V3AUX_39") (pintype "bidirectional"))
      (node (ref "X1") (pin "41") (pinfunction "+3V3AUX_41") (pintype "bidirectional"))
      (node (ref "X1") (pin "52") (pinfunction "+3V3_52") (pintype "power_in"))
    )
    (net (code "47") (name "VDD_1V5") (class "Default")
      (node (ref "X1") (pin "28") (pinfunction "+1V5_28") (pintype "power_in"))
      (node (ref "X1") (pin "48") (pinfunction "+1V5_48") (pintype "output"))
      (node (ref "X1") (pin "6") (pinfunction "+1V5_6") (pintype "power_in"))
    )
    (net (code "48") (name "WAKE") (class "Default")
      (node (ref "JP4") (pin "2") (pinfunction "2_2") (pintype "passive"))
      (node (ref "X1") (pin "1") (pinfunction "WAKE_1") (pintype "output"))
    )
    (net (code "49") (name "unconnected-(X2-Pad4)") (class "Default")
      (node (ref "X2") (pin "4") (pinfunction "4_4") (pintype "input"))
    )
  )
)
